# CAN_PHY.net
KiCad netlist of a schematic drawn in Altium Designer
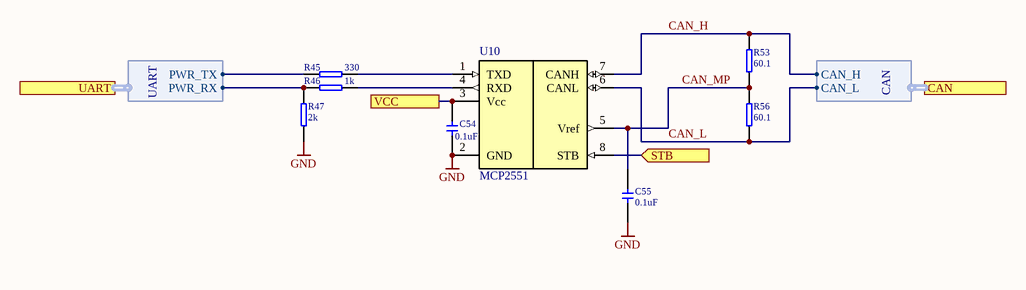
[diagram p0: CAN_PHY.SchDoc]

(export (version "E")
  (design (tool "Eeschema 10.0.6"))
  (components
    (comp (ref "C54")
      (value "0.1uF")
      (footprint "CERCAP 0402")
      (description "Capacitor")
      (fields (field (name "VOLTAGE") "50V") (field (name "Comment") "CERCAP 0402 0.1uF 50V X7R"))
      (libsource (lib "!main") (part "!Capacitor"))
    )
    (comp (ref "C55")
      (value "0.1uF")
      (footprint "CERCAP 0402")
      (description "Capacitor")
      (fields (field (name "VOLTAGE") "50V") (field (name "Comment") "CERCAP 0402 0.1uF 50V X7R"))
      (libsource (lib "!main") (part "!Capacitor"))
    )
    (comp (ref "R45")
      (value "330")
      (footprint "RES 0402")
      (description "Resistor")
      (fields (field (name "Comment") "RES 0402 330"))
      (libsource (lib "!main") (part "!Resistor"))
    )
    (comp (ref "R46")
      (value "1k")
      (footprint "RES 0402")
      (description "Resistor")
      (fields (field (name "Comment") "RES 0402 1k"))
      (libsource (lib "!main") (part "!Resistor"))
    )
    (comp (ref "R47")
      (value "2k")
      (footprint "RES 0402")
      (description "Resistor")
      (fields (field (name "Comment") "RES 0402 2k"))
      (libsource (lib "!main") (part "!Resistor"))
    )
    (comp (ref "R53")
      (value "60.1")
      (footprint "RES 0402")
      (description "Resistor")
      (fields (field (name "Comment") "RES 0402 60.1"))
      (libsource (lib "!main") (part "!Resistor"))
    )
    (comp (ref "R56")
      (value "60.1")
      (footprint "RES 0402")
      (description "Resistor")
      (fields (field (name "Comment") "RES 0402 60.1"))
      (libsource (lib "!main") (part "!Resistor"))
    )
    (comp (ref "U10")
      (value "MCP2551")
      (footprint "SO-8")
      (description "CAN PHY")
      (libsource (lib "interfaces") (part "CAN_PHY"))
    )
  )
  (nets
    (net (code "3") (name "/CAN_H") (class "Default")
      (node (ref "R53") (pin "2") (pinfunction "12_2") (pintype "passive"))
      (node (ref "U10") (pin "7") (pinfunction "CANH_7") (pintype "bidirectional"))
    )
    (net (code "4") (name "/CAN_L") (class "Default")
      (node (ref "R56") (pin "1") (pinfunction "11_1") (pintype "passive"))
      (node (ref "U10") (pin "6") (pinfunction "CANL_6") (pintype "bidirectional"))
    )
    (net (code "5") (name "/CAN_MP") (class "Default")
      (node (ref "C55") (pin "2") (pintype "passive"))
      (node (ref "R53") (pin "1") (pinfunction "11_1") (pintype "passive"))
      (node (ref "R56") (pin "2") (pinfunction "12_2") (pintype "passive"))
      (node (ref "U10") (pin "5") (pinfunction "Vref_5") (pintype "output"))
    )
    (net (code "6") (name "/PWR_RX") (class "Default")
      (node (ref "R46") (pin "1") (pinfunction "11_1") (pintype "passive"))
      (node (ref "R47") (pin "2") (pinfunction "12_2") (pintype "passive"))
    )
    (net (code "7") (name "/PWR_TX") (class "Default")
      (node (ref "R45") (pin "1") (pinfunction "11_1") (pintype "passive"))
    )
    (net (code "8") (name "/STB") (class "Default")
      (node (ref "U10") (pin "8") (pinfunction "STB_8") (pintype "input"))
    )
    (net (code "9") (name "/VCC") (class "Default")
      (node (ref "C54") (pin "2") (pintype "passive"))
      (node (ref "U10") (pin "3") (pinfunction "Vcc_3") (pintype "power_in"))
    )
    (net (code "12") (name "GND") (class "Default")
      (node (ref "C54") (pin "1") (pintype "passive"))
      (node (ref "C55") (pin "1") (pintype "passive"))
      (node (ref "R47") (pin "1") (pinfunction "11_1") (pintype "passive"))
      (node (ref "U10") (pin "2") (pinfunction "GND_2") (pintype "power_in"))
    )
    (net (code "13") (name "Net-(R45-12)") (class "Default")
      (node (ref "R45") (pin "2") (pinfunction "12_2") (pintype "passive"))
      (node (ref "U10") (pin "1") (pinfunction "TXD_1") (pintype "input"))
    )
    (net (code "14") (name "Net-(R46-12)") (class "Default")
      (node (ref "R46") (pin "2") (pinfunction "12_2") (pintype "passive"))
      (node (ref "U10") (pin "4") (pinfunction "RXD_4") (pintype "output"))
    )
  )
)
